# CSR8645-VFBGA275um-V1.net
KiCad netlist of a schematic drawn in EAGLE
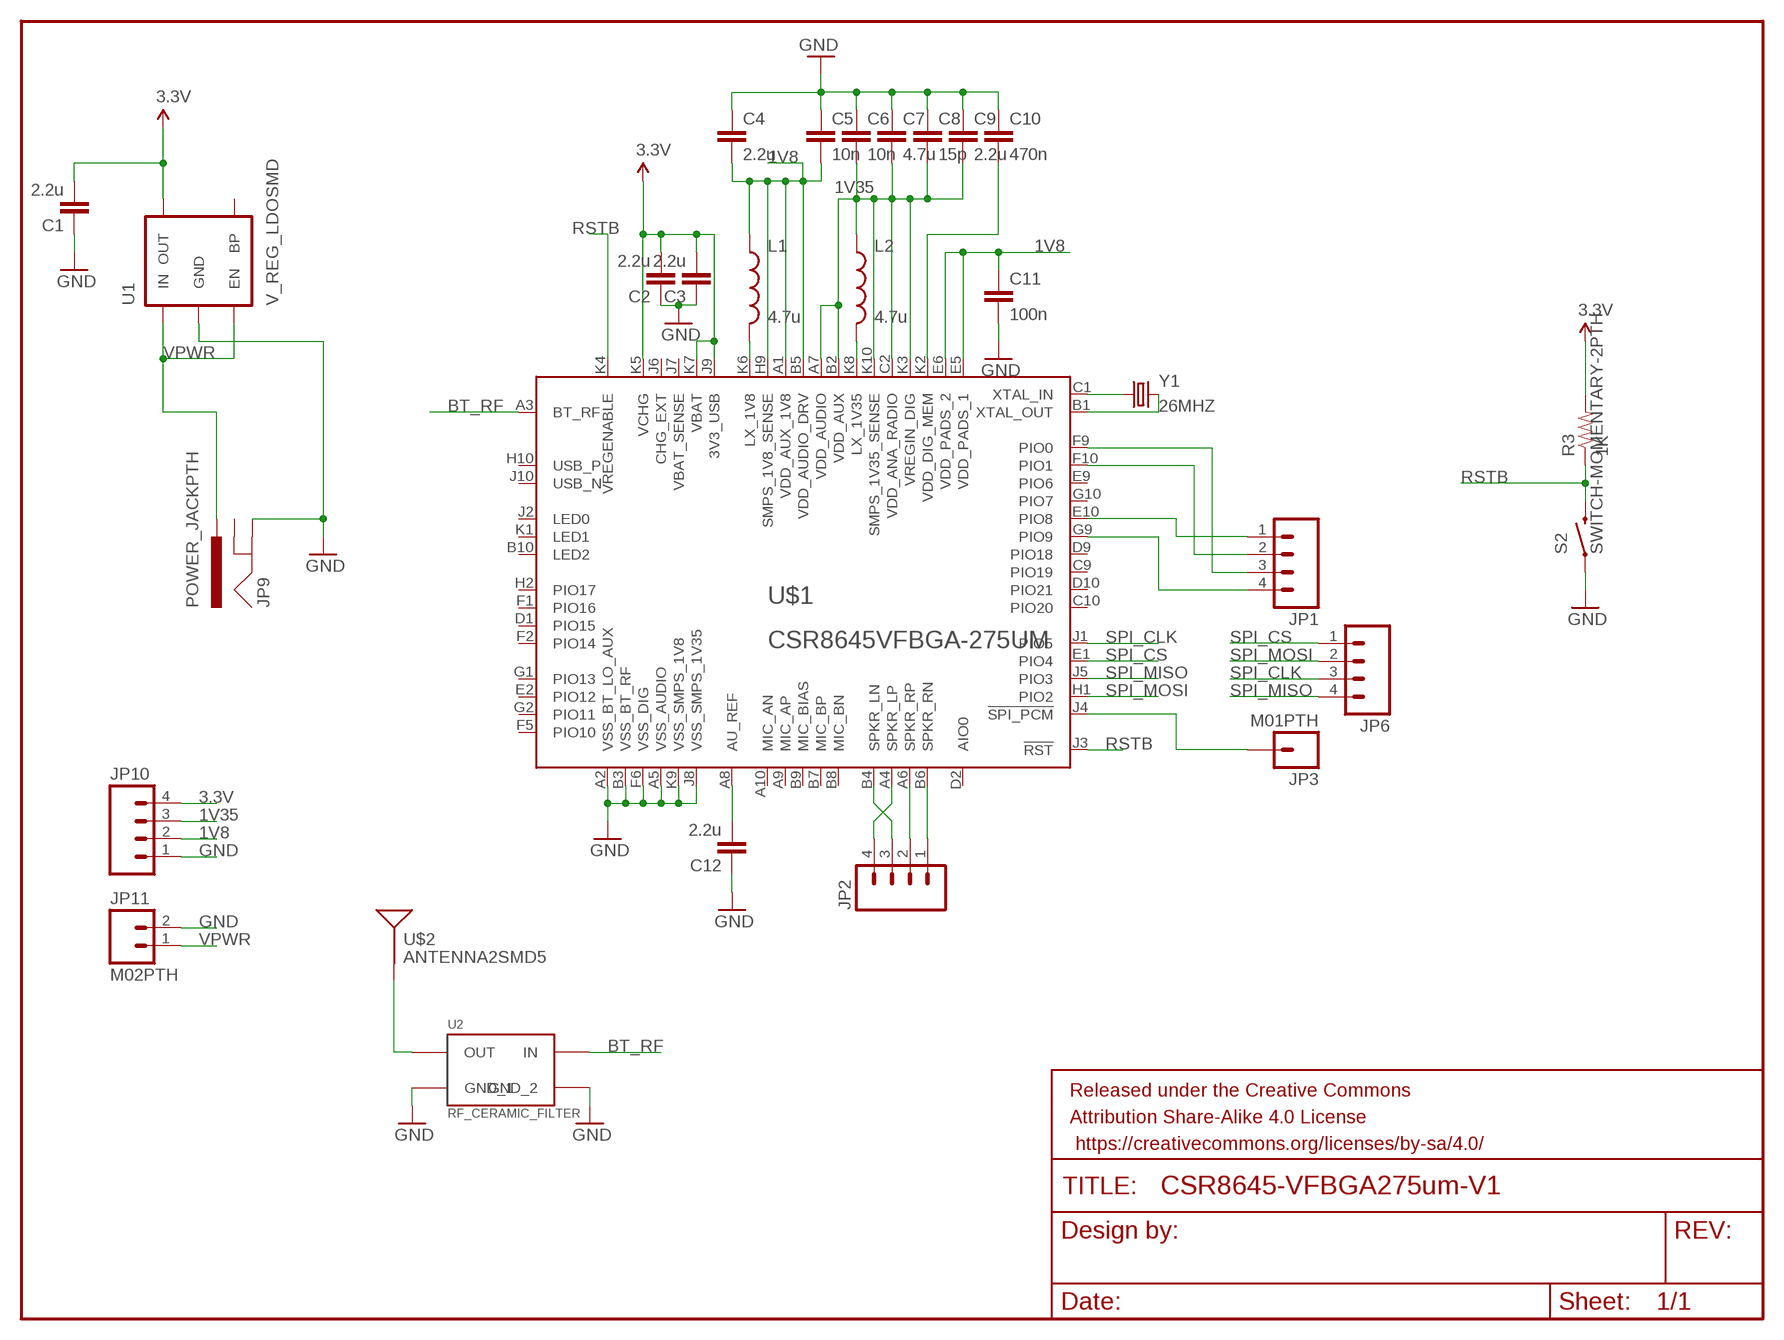
[diagram p0: schematic, sheet 1]

(export (version "E")
  (design (tool "Eeschema 10.0.6"))
  (components
    (comp (ref "C1")
      (value "2.2u")
      (footprint "eagle-import:CAP-PTH-SMALL")
      (libsource (lib "eagle-import") (part "CAPPTH"))
    )
    (comp (ref "C2")
      (value "2.2u")
      (footprint "eagle-import:CAP-PTH-SMALL")
      (libsource (lib "eagle-import") (part "CAPPTH"))
    )
    (comp (ref "C3")
      (value "2.2u")
      (footprint "eagle-import:CAP-PTH-SMALL")
      (libsource (lib "eagle-import") (part "CAPPTH"))
    )
    (comp (ref "C4")
      (value "2.2u")
      (footprint "eagle-import:CAP-PTH-SMALL")
      (libsource (lib "eagle-import") (part "CAPPTH"))
    )
    (comp (ref "C5")
      (value "10n")
      (footprint "eagle-import:CAP-PTH-SMALL")
      (libsource (lib "eagle-import") (part "CAPPTH"))
    )
    (comp (ref "C6")
      (value "10n")
      (footprint "eagle-import:CAP-PTH-SMALL")
      (libsource (lib "eagle-import") (part "CAPPTH"))
    )
    (comp (ref "C7")
      (value "4.7u")
      (footprint "eagle-import:CAP-PTH-SMALL")
      (libsource (lib "eagle-import") (part "CAPPTH"))
    )
    (comp (ref "C8")
      (value "15p")
      (footprint "eagle-import:CAP-PTH-SMALL")
      (libsource (lib "eagle-import") (part "CAPPTH"))
    )
    (comp (ref "C9")
      (value "2.2u")
      (footprint "eagle-import:CAP-PTH-SMALL")
      (libsource (lib "eagle-import") (part "CAPPTH"))
    )
    (comp (ref "C10")
      (value "470n")
      (footprint "eagle-import:CAP-PTH-SMALL")
      (libsource (lib "eagle-import") (part "CAPPTH"))
    )
    (comp (ref "C11")
      (value "100n")
      (footprint "eagle-import:CAP-PTH-SMALL")
      (libsource (lib "eagle-import") (part "CAPPTH"))
    )
    (comp (ref "C12")
      (value "2.2u")
      (footprint "eagle-import:CAP-PTH-SMALL")
      (libsource (lib "eagle-import") (part "CAPPTH"))
    )
    (comp (ref "FRAME1")
      (value "FRAME-LETTER")
      (footprint "eagle-import:CREATIVE_COMMONS")
      (libsource (lib "eagle-import") (part "FRAME-LETTER"))
    )
    (comp (ref "JP1")
      (value "M04PTH")
      (footprint "eagle-import:1X04")
      (libsource (lib "eagle-import") (part "M04PTH"))
    )
    (comp (ref "JP2")
      (value "M04PTH")
      (footprint "eagle-import:1X04")
      (libsource (lib "eagle-import") (part "M04PTH"))
    )
    (comp (ref "JP3")
      (value "M01PTH")
      (footprint "eagle-import:1X01")
      (libsource (lib "eagle-import") (part "M01PTH"))
    )
    (comp (ref "JP6")
      (value "M04PTH")
      (footprint "eagle-import:1X04")
      (libsource (lib "eagle-import") (part "M04PTH"))
    )
    (comp (ref "JP9")
      (value "POWER_JACKPTH")
      (footprint "eagle-import:POWER_JACK_PTH")
      (libsource (lib "eagle-import") (part "POWER_JACKPTH"))
    )
    (comp (ref "JP10")
      (value "M04PTH")
      (footprint "eagle-import:1X04")
      (libsource (lib "eagle-import") (part "M04PTH"))
    )
    (comp (ref "JP11")
      (value "M02PTH")
      (footprint "eagle-import:1X02")
      (libsource (lib "eagle-import") (part "M02PTH"))
    )
    (comp (ref "L1")
      (value "4.7u")
      (footprint "eagle-import:0805")
      (libsource (lib "eagle-import") (part "INDUCTOR0805"))
    )
    (comp (ref "L2")
      (value "4.7u")
      (footprint "eagle-import:0805")
      (libsource (lib "eagle-import") (part "INDUCTOR0805"))
    )
    (comp (ref "R3")
      (value "1K")
      (footprint "eagle-import:0805")
      (libsource (lib "eagle-import") (part "RESISTOR0805-RES"))
    )
    (comp (ref "S2")
      (value "SWITCH-MOMENTARY-2PTH")
      (footprint "eagle-import:TACTILE-PTH")
      (libsource (lib "eagle-import") (part "SWITCH-MOMENTARY-2PTH"))
    )
    (comp (ref "U$1")
      (value "CSR8645VFBGA-275UM")
      (footprint "eagle-import:VFBGA68-LARGE")
      (libsource (lib "eagle-import") (part "CSR8645VFBGA-275UM"))
    )
    (comp (ref "U$2")
      (value "ANTENNA2SMD5")
      (footprint "eagle-import:ANTENNA-CHIP5")
      (libsource (lib "eagle-import") (part "ANTENNA2SMD5"))
    )
    (comp (ref "U1")
      (value "V_REG_LDOSMD")
      (footprint "eagle-import:SOT23-5")
      (libsource (lib "eagle-import") (part "V_REG_LDOSMD"))
    )
    (comp (ref "U2")
      (value "RF_CERAMIC_FILTER")
      (footprint "eagle-import:RF_FILTER")
      (libsource (lib "eagle-import") (part "RF_CERAMIC_FILTER"))
    )
    (comp (ref "Y1")
      (value "26MHZ")
      (footprint "eagle-import:HC49US")
      (libsource (lib "eagle-import") (part "CRYSTALHC49US"))
    )
  )
  (nets
    (net (code "1") (name "/1V8") (class "Default")
      (node (ref "C11") (pin "1") (pinfunction "1_1") (pintype "passive"))
      (node (ref "C4") (pin "2") (pinfunction "2_2") (pintype "passive"))
      (node (ref "C5") (pin "2") (pinfunction "2_2") (pintype "passive"))
      (node (ref "JP10") (pin "2") (pinfunction "2_2") (pintype "passive"))
      (node (ref "L1") (pin "1") (pinfunction "1_1") (pintype "passive"))
      (node (ref "U$1") (pin "A1") (pinfunction "VDD_AUX_1V8_A1") (pintype "bidirectional"))
      (node (ref "U$1") (pin "B5") (pinfunction "VDD_AUDIO_DRV_B5") (pintype "bidirectional"))
      (node (ref "U$1") (pin "E5") (pinfunction "VDD_PADS_1_E5") (pintype "bidirectional"))
      (node (ref "U$1") (pin "E6") (pinfunction "VDD_PADS_2_E6") (pintype "bidirectional"))
      (node (ref "U$1") (pin "H9") (pinfunction "SMPS_1V8_SENSE_H9") (pintype "bidirectional"))
    )
    (net (code "2") (name "/1V35") (class "Default")
      (node (ref "C6") (pin "2") (pinfunction "2_2") (pintype "passive"))
      (node (ref "C7") (pin "2") (pinfunction "2_2") (pintype "passive"))
      (node (ref "C8") (pin "2") (pinfunction "2_2") (pintype "passive"))
      (node (ref "C9") (pin "2") (pinfunction "2_2") (pintype "passive"))
      (node (ref "JP10") (pin "3") (pinfunction "3_3") (pintype "passive"))
      (node (ref "L2") (pin "1") (pinfunction "1_1") (pintype "passive"))
      (node (ref "U$1") (pin "A7") (pinfunction "VDD_AUDIO_A7") (pintype "bidirectional"))
      (node (ref "U$1") (pin "B2") (pinfunction "VDD_AUX_B2") (pintype "bidirectional"))
      (node (ref "U$1") (pin "C2") (pinfunction "VDD_ANA_RADIO_C2") (pintype "bidirectional"))
      (node (ref "U$1") (pin "K10") (pinfunction "SMPS_1V35_SENSE_K10") (pintype "bidirectional"))
      (node (ref "U$1") (pin "K3") (pinfunction "VREGIN_DIG_K3") (pintype "bidirectional"))
    )
    (net (code "3") (name "/BT_RF") (class "Default")
      (node (ref "U$1") (pin "A3") (pinfunction "BT_RF_A3") (pintype "bidirectional"))
      (node (ref "U2") (pin "4") (pinfunction "IN_4") (pintype "bidirectional"))
    )
    (net (code "4") (name "/RSTB") (class "Default")
      (node (ref "R3") (pin "1") (pinfunction "1_1") (pintype "passive"))
      (node (ref "S2") (pin "3") (pinfunction "2_3") (pintype "passive"))
      (node (ref "U$1") (pin "J3") (pinfunction "~{RST}_J3") (pintype "input"))
      (node (ref "U$1") (pin "K4") (pinfunction "VREGENABLE_K4") (pintype "bidirectional"))
    )
    (net (code "5") (name "/SPI_CLK") (class "Default")
      (node (ref "JP6") (pin "3") (pinfunction "3_3") (pintype "passive"))
      (node (ref "U$1") (pin "J1") (pinfunction "PIO5_J1") (pintype "bidirectional"))
    )
    (net (code "6") (name "/SPI_CS") (class "Default")
      (node (ref "JP6") (pin "1") (pinfunction "1_1") (pintype "passive"))
      (node (ref "U$1") (pin "E1") (pinfunction "PIO4_E1") (pintype "bidirectional"))
    )
    (net (code "7") (name "/SPI_MISO") (class "Default")
      (node (ref "JP6") (pin "4") (pinfunction "4_4") (pintype "passive"))
      (node (ref "U$1") (pin "J5") (pinfunction "PIO3_J5") (pintype "bidirectional"))
    )
    (net (code "8") (name "/SPI_MOSI") (class "Default")
      (node (ref "JP6") (pin "2") (pinfunction "2_2") (pintype "passive"))
      (node (ref "U$1") (pin "H1") (pinfunction "PIO2_H1") (pintype "bidirectional"))
    )
    (net (code "9") (name "/VPWR") (class "Default")
      (node (ref "JP11") (pin "1") (pinfunction "1_1") (pintype "passive"))
      (node (ref "JP9") (pin "PWR") (pinfunction "PWR_PWR") (pintype "bidirectional"))
      (node (ref "U1") (pin "1") (pinfunction "IN_1") (pintype "input"))
      (node (ref "U1") (pin "3") (pinfunction "EN_3") (pintype "input"))
    )
    (net (code "10") (name "3.3V") (class "Default")
      (node (ref "C1") (pin "2") (pinfunction "2_2") (pintype "passive"))
      (node (ref "C2") (pin "2") (pinfunction "2_2") (pintype "passive"))
      (node (ref "C3") (pin "2") (pinfunction "2_2") (pintype "passive"))
      (node (ref "JP10") (pin "4") (pinfunction "4_4") (pintype "passive"))
      (node (ref "R3") (pin "2") (pinfunction "2_2") (pintype "passive"))
      (node (ref "U$1") (pin "J9") (pinfunction "3V3_USB_J9") (pintype "power_in"))
      (node (ref "U$1") (pin "K5") (pinfunction "VCHG_K5") (pintype "power_in"))
      (node (ref "U$1") (pin "K7") (pinfunction "VBAT_K7") (pintype "power_in"))
      (node (ref "U1") (pin "5") (pinfunction "OUT_5") (pintype "passive"))
    )
    (net (code "11") (name "GND") (class "Default")
      (node (ref "C1") (pin "1") (pinfunction "1_1") (pintype "passive"))
      (node (ref "C10") (pin "1") (pinfunction "1_1") (pintype "passive"))
      (node (ref "C11") (pin "2") (pinfunction "2_2") (pintype "passive"))
      (node (ref "C12") (pin "1") (pinfunction "1_1") (pintype "passive"))
      (node (ref "C2") (pin "1") (pinfunction "1_1") (pintype "passive"))
      (node (ref "C3") (pin "1") (pinfunction "1_1") (pintype "passive"))
      (node (ref "C4") (pin "1") (pinfunction "1_1") (pintype "passive"))
      (node (ref "C5") (pin "1") (pinfunction "1_1") (pintype "passive"))
      (node (ref "C6") (pin "1") (pinfunction "1_1") (pintype "passive"))
      (node (ref "C7") (pin "1") (pinfunction "1_1") (pintype "passive"))
      (node (ref "C8") (pin "1") (pinfunction "1_1") (pintype "passive"))
      (node (ref "C9") (pin "1") (pinfunction "1_1") (pintype "passive"))
      (node (ref "JP10") (pin "1") (pinfunction "1_1") (pintype "passive"))
      (node (ref "JP11") (pin "2") (pinfunction "2_2") (pintype "passive"))
      (node (ref "JP9") (pin "GND") (pinfunction "GND_GND") (pintype "bidirectional"))
      (node (ref "S2") (pin "1") (pinfunction "1_1") (pintype "passive"))
      (node (ref "U$1") (pin "A2") (pinfunction "VSS_BT_LO_AUX_A2") (pintype "bidirectional"))
      (node (ref "U$1") (pin "A5") (pinfunction "VSS_AUDIO_A5") (pintype "bidirectional"))
      (node (ref "U$1") (pin "B3") (pinfunction "VSS_BT_RF_B3") (pintype "bidirectional"))
      (node (ref "U$1") (pin "F6") (pinfunction "VSS_DIG_F6") (pintype "bidirectional"))
      (node (ref "U$1") (pin "J8") (pinfunction "VSS_SMPS_1V35_J8") (pintype "bidirectional"))
      (node (ref "U$1") (pin "K9") (pinfunction "VSS_SMPS_1V8_K9") (pintype "bidirectional"))
      (node (ref "U1") (pin "2") (pinfunction "GND_2") (pintype "input"))
      (node (ref "U2") (pin "1") (pinfunction "GND_1_1") (pintype "power_in"))
      (node (ref "U2") (pin "3") (pinfunction "GND_2_3") (pintype "power_in"))
    )
    (net (code "12") (name "Net-(U$1-AU_REF)") (class "Default")
      (node (ref "C12") (pin "2") (pinfunction "2_2") (pintype "passive"))
      (node (ref "U$1") (pin "A8") (pinfunction "AU_REF_A8") (pintype "input"))
    )
    (net (code "13") (name "Net-(U$1-LX_1V8)") (class "Default")
      (node (ref "L1") (pin "2") (pinfunction "2_2") (pintype "passive"))
      (node (ref "U$1") (pin "K6") (pinfunction "LX_1V8_K6") (pintype "bidirectional"))
    )
    (net (code "14") (name "Net-(U$1-LX_1V35)") (class "Default")
      (node (ref "L2") (pin "2") (pinfunction "2_2") (pintype "passive"))
      (node (ref "U$1") (pin "K8") (pinfunction "LX_1V35_K8") (pintype "bidirectional"))
    )
    (net (code "15") (name "Net-(U$1-PIO0)") (class "Default")
      (node (ref "JP1") (pin "3") (pinfunction "3_3") (pintype "passive"))
      (node (ref "U$1") (pin "F9") (pinfunction "PIO0_F9") (pintype "bidirectional"))
    )
    (net (code "16") (name "Net-(U$1-PIO1)") (class "Default")
      (node (ref "JP1") (pin "2") (pinfunction "2_2") (pintype "passive"))
      (node (ref "U$1") (pin "F10") (pinfunction "PIO1_F10") (pintype "bidirectional"))
    )
    (net (code "17") (name "Net-(U$1-PIO8)") (class "Default")
      (node (ref "JP1") (pin "1") (pinfunction "1_1") (pintype "passive"))
      (node (ref "U$1") (pin "E10") (pinfunction "PIO8_E10") (pintype "bidirectional"))
    )
    (net (code "18") (name "Net-(U$1-PIO9)") (class "Default")
      (node (ref "JP1") (pin "4") (pinfunction "4_4") (pintype "passive"))
      (node (ref "U$1") (pin "G9") (pinfunction "PIO9_G9") (pintype "bidirectional"))
    )
    (net (code "19") (name "Net-(U$1-SPKR_LN)") (class "Default")
      (node (ref "JP2") (pin "3") (pinfunction "3_3") (pintype "passive"))
      (node (ref "U$1") (pin "B4") (pinfunction "SPKR_LN_B4") (pintype "output"))
    )
    (net (code "20") (name "Net-(U$1-SPKR_LP)") (class "Default")
      (node (ref "JP2") (pin "4") (pinfunction "4_4") (pintype "passive"))
      (node (ref "U$1") (pin "A4") (pinfunction "SPKR_LP_A4") (pintype "output"))
    )
    (net (code "21") (name "Net-(U$1-SPKR_RN)") (class "Default")
      (node (ref "JP2") (pin "1") (pinfunction "1_1") (pintype "passive"))
      (node (ref "U$1") (pin "B6") (pinfunction "SPKR_RN_B6") (pintype "output"))
    )
    (net (code "22") (name "Net-(U$1-SPKR_RP)") (class "Default")
      (node (ref "JP2") (pin "2") (pinfunction "2_2") (pintype "passive"))
      (node (ref "U$1") (pin "A6") (pinfunction "SPKR_RP_A6") (pintype "output"))
    )
    (net (code "23") (name "Net-(U$1-VDD_DIG_MEM)") (class "Default")
      (node (ref "C10") (pin "2") (pinfunction "2_2") (pintype "passive"))
      (node (ref "U$1") (pin "K2") (pinfunction "VDD_DIG_MEM_K2") (pintype "bidirectional"))
    )
    (net (code "24") (name "Net-(U$1-XTAL_IN)") (class "Default")
      (node (ref "U$1") (pin "C1") (pinfunction "XTAL_IN_C1") (pintype "input"))
      (node (ref "Y1") (pin "1") (pinfunction "1_1") (pintype "passive"))
    )
    (net (code "25") (name "Net-(U$1-XTAL_OUT)") (class "Default")
      (node (ref "U$1") (pin "B1") (pinfunction "XTAL_OUT_B1") (pintype "bidirectional"))
      (node (ref "Y1") (pin "2") (pinfunction "2_2") (pintype "passive"))
    )
    (net (code "26") (name "Net-(U$1-~{SPI_PCM})") (class "Default")
      (node (ref "JP3") (pin "1") (pinfunction "1_1") (pintype "passive"))
      (node (ref "U$1") (pin "J4") (pinfunction "~{SPI_PCM}_J4") (pintype "input"))
    )
    (net (code "27") (name "Net-(U$2-SIGNAL)") (class "Default")
      (node (ref "U$2") (pin "FEED") (pinfunction "SIGNAL_FEED") (pintype "bidirectional"))
      (node (ref "U2") (pin "2") (pinfunction "OUT_2") (pintype "bidirectional"))
    )
    (net (code "28") (name "unconnected-(JP9-PadGNDBREAK)") (class "Default")
      (node (ref "JP9") (pin "GNDBREAK") (pinfunction "GNDBREAK_GNDBREAK") (pintype "bidirectional"))
    )
    (net (code "29") (name "unconnected-(U$1-AIO0-PadD2)") (class "Default")
      (node (ref "U$1") (pin "D2") (pinfunction "AIO0_D2") (pintype "bidirectional"))
    )
    (net (code "30") (name "unconnected-(U$1-CHG_EXT-PadJ6)") (class "Default")
      (node (ref "U$1") (pin "J6") (pinfunction "CHG_EXT_J6") (pintype "bidirectional"))
    )
    (net (code "31") (name "unconnected-(U$1-LED0-PadJ2)") (class "Default")
      (node (ref "U$1") (pin "J2") (pinfunction "LED0_J2") (pintype "bidirectional"))
    )
    (net (code "32") (name "unconnected-(U$1-LED1-PadK1)") (class "Default")
      (node (ref "U$1") (pin "K1") (pinfunction "LED1_K1") (pintype "bidirectional"))
    )
    (net (code "33") (name "unconnected-(U$1-LED2-PadB10)") (class "Default")
      (node (ref "U$1") (pin "B10") (pinfunction "LED2_B10") (pintype "bidirectional"))
    )
    (net (code "34") (name "unconnected-(U$1-MIC_AN-PadA10)") (class "Default")
      (node (ref "U$1") (pin "A10") (pinfunction "MIC_AN_A10") (pintype "input"))
    )
    (net (code "35") (name "unconnected-(U$1-MIC_AP-PadA9)") (class "Default")
      (node (ref "U$1") (pin "A9") (pinfunction "MIC_AP_A9") (pintype "input"))
    )
    (net (code "36") (name "unconnected-(U$1-MIC_BIAS-PadB9)") (class "Default")
      (node (ref "U$1") (pin "B9") (pinfunction "MIC_BIAS_B9") (pintype "output"))
    )
    (net (code "37") (name "unconnected-(U$1-MIC_BN-PadB8)") (class "Default")
      (node (ref "U$1") (pin "B8") (pinfunction "MIC_BN_B8") (pintype "input"))
    )
    (net (code "38") (name "unconnected-(U$1-MIC_BP-PadB7)") (class "Default")
      (node (ref "U$1") (pin "B7") (pinfunction "MIC_BP_B7") (pintype "input"))
    )
    (net (code "39") (name "unconnected-(U$1-PIO6-PadE9)") (class "Default")
      (node (ref "U$1") (pin "E9") (pinfunction "PIO6_E9") (pintype "bidirectional"))
    )
    (net (code "40") (name "unconnected-(U$1-PIO7-PadG10)") (class "Default")
      (node (ref "U$1") (pin "G10") (pinfunction "PIO7_G10") (pintype "bidirectional"))
    )
    (net (code "41") (name "unconnected-(U$1-PIO10-PadF5)") (class "Default")
      (node (ref "U$1") (pin "F5") (pinfunction "PIO10_F5") (pintype "bidirectional"))
    )
    (net (code "42") (name "unconnected-(U$1-PIO11-PadG2)") (class "Default")
      (node (ref "U$1") (pin "G2") (pinfunction "PIO11_G2") (pintype "bidirectional"))
    )
    (net (code "43") (name "unconnected-(U$1-PIO12-PadE2)") (class "Default")
      (node (ref "U$1") (pin "E2") (pinfunction "PIO12_E2") (pintype "bidirectional"))
    )
    (net (code "44") (name "unconnected-(U$1-PIO13-PadG1)") (class "Default")
      (node (ref "U$1") (pin "G1") (pinfunction "PIO13_G1") (pintype "bidirectional"))
    )
    (net (code "45") (name "unconnected-(U$1-PIO14-PadF2)") (class "Default")
      (node (ref "U$1") (pin "F2") (pinfunction "PIO14_F2") (pintype "bidirectional"))
    )
    (net (code "46") (name "unconnected-(U$1-PIO15-PadD1)") (class "Default")
      (node (ref "U$1") (pin "D1") (pinfunction "PIO15_D1") (pintype "bidirectional"))
    )
    (net (code "47") (name "unconnected-(U$1-PIO16-PadF1)") (class "Default")
      (node (ref "U$1") (pin "F1") (pinfunction "PIO16_F1") (pintype "bidirectional"))
    )
    (net (code "48") (name "unconnected-(U$1-PIO17-PadH2)") (class "Default")
      (node (ref "U$1") (pin "H2") (pinfunction "PIO17_H2") (pintype "bidirectional"))
    )
    (net (code "49") (name "unconnected-(U$1-PIO18-PadD9)") (class "Default")
      (node (ref "U$1") (pin "D9") (pinfunction "PIO18_D9") (pintype "bidirectional"))
    )
    (net (code "50") (name "unconnected-(U$1-PIO19-PadC9)") (class "Default")
      (node (ref "U$1") (pin "C9") (pinfunction "PIO19_C9") (pintype "bidirectional"))
    )
    (net (code "51") (name "unconnected-(U$1-PIO20-PadC10)") (class "Default")
      (node (ref "U$1") (pin "C10") (pinfunction "PIO20_C10") (pintype "bidirectional"))
    )
    (net (code "52") (name "unconnected-(U$1-PIO21-PadD10)") (class "Default")
      (node (ref "U$1") (pin "D10") (pinfunction "PIO21_D10") (pintype "bidirectional"))
    )
    (net (code "53") (name "unconnected-(U$1-USB_N-PadJ10)") (class "Default")
      (node (ref "U$1") (pin "J10") (pinfunction "USB_N_J10") (pintype "bidirectional"))
    )
    (net (code "54") (name "unconnected-(U$1-USB_P-PadH10)") (class "Default")
      (node (ref "U$1") (pin "H10") (pinfunction "USB_P_H10") (pintype "bidirectional"))
    )
    (net (code "55") (name "unconnected-(U$1-VBAT_SENSE-PadJ7)") (class "Default")
      (node (ref "U$1") (pin "J7") (pinfunction "VBAT_SENSE_J7") (pintype "bidirectional"))
    )
    (net (code "56") (name "unconnected-(U1-BP-Pad4)") (class "Default")
      (node (ref "U1") (pin "4") (pinfunction "BP_4") (pintype "input"))
    )
  )
)
